# Maqam_v2.net
KiCad netlist of a schematic drawn in EAGLE
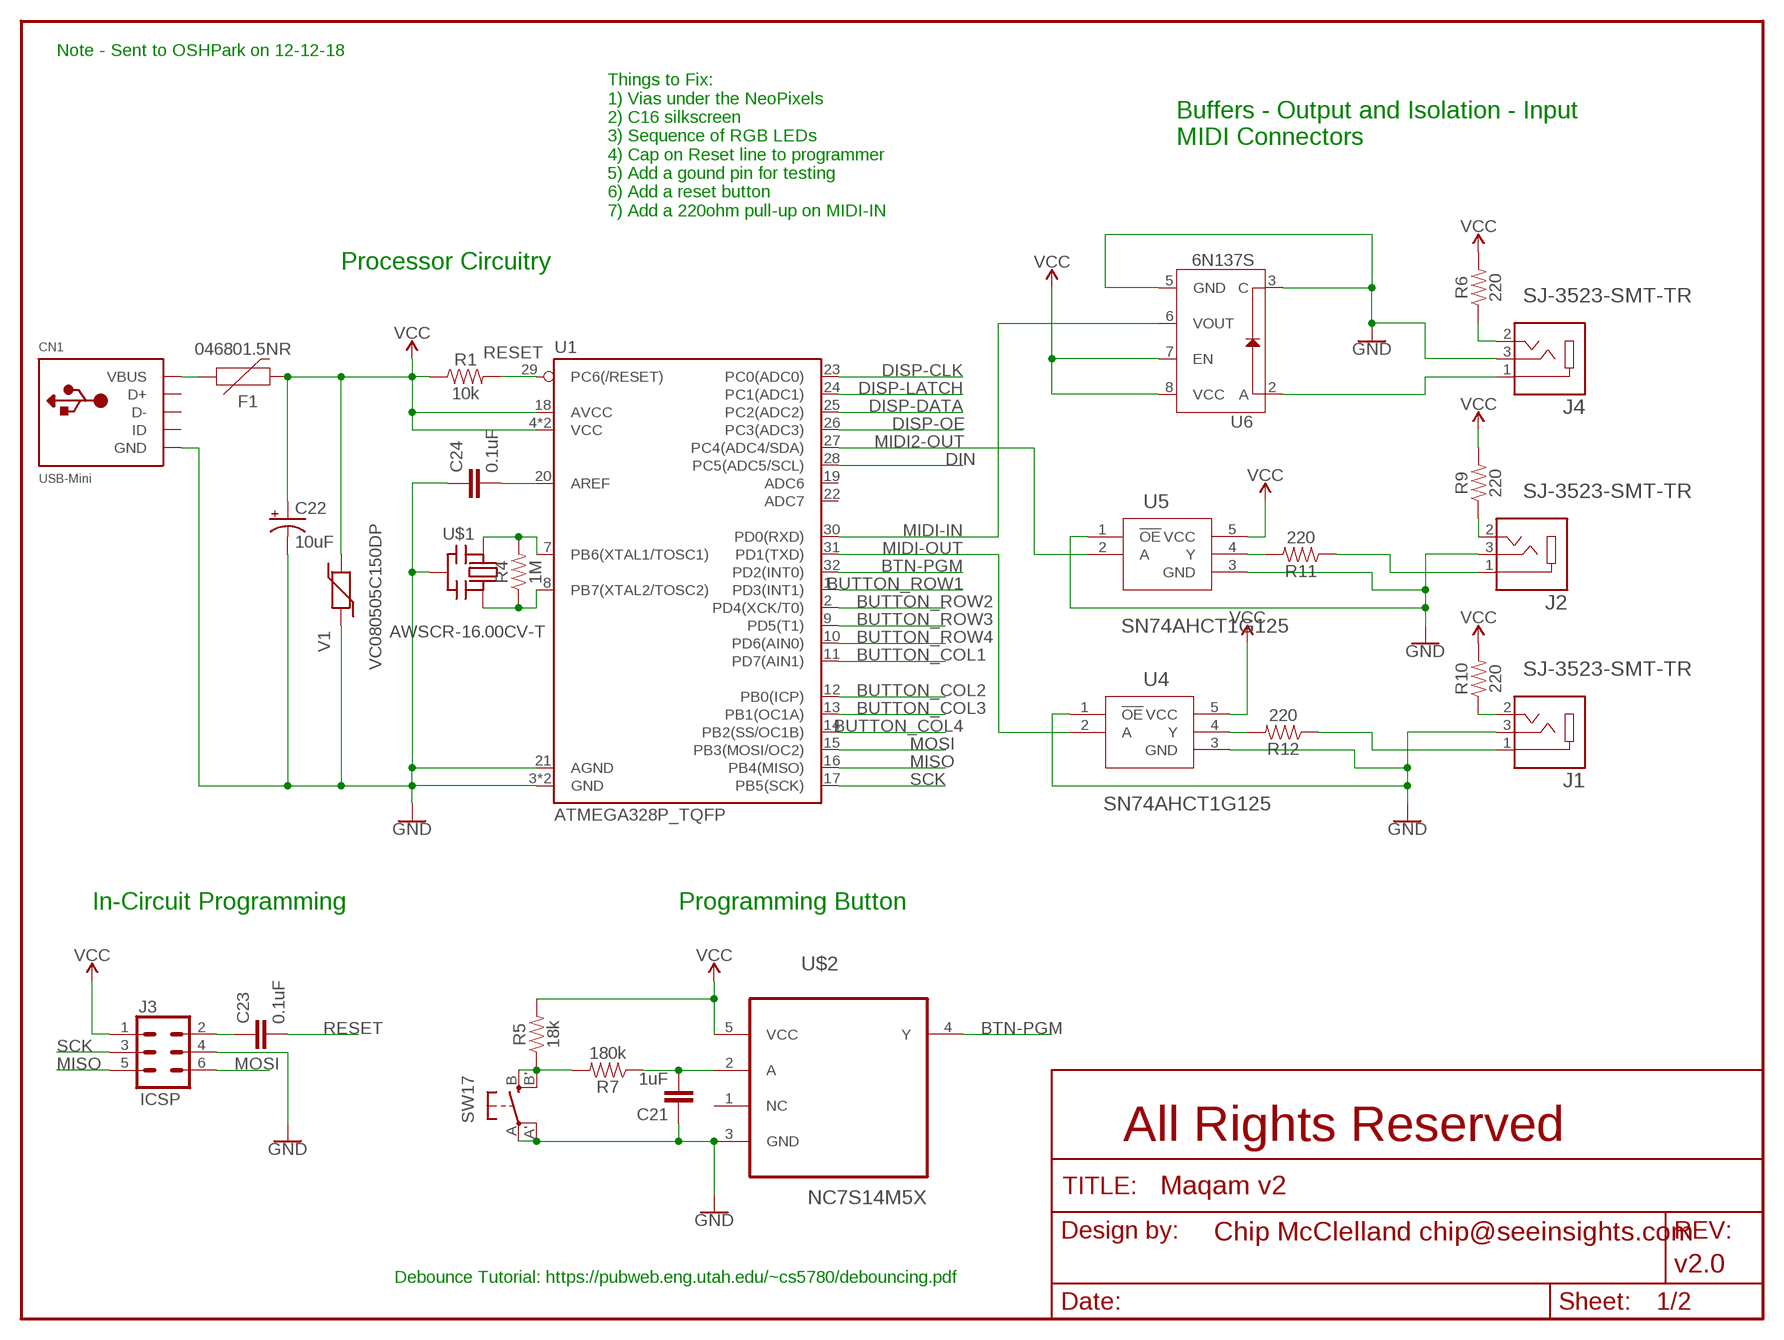
[diagram p0: schematic, sheet 1]
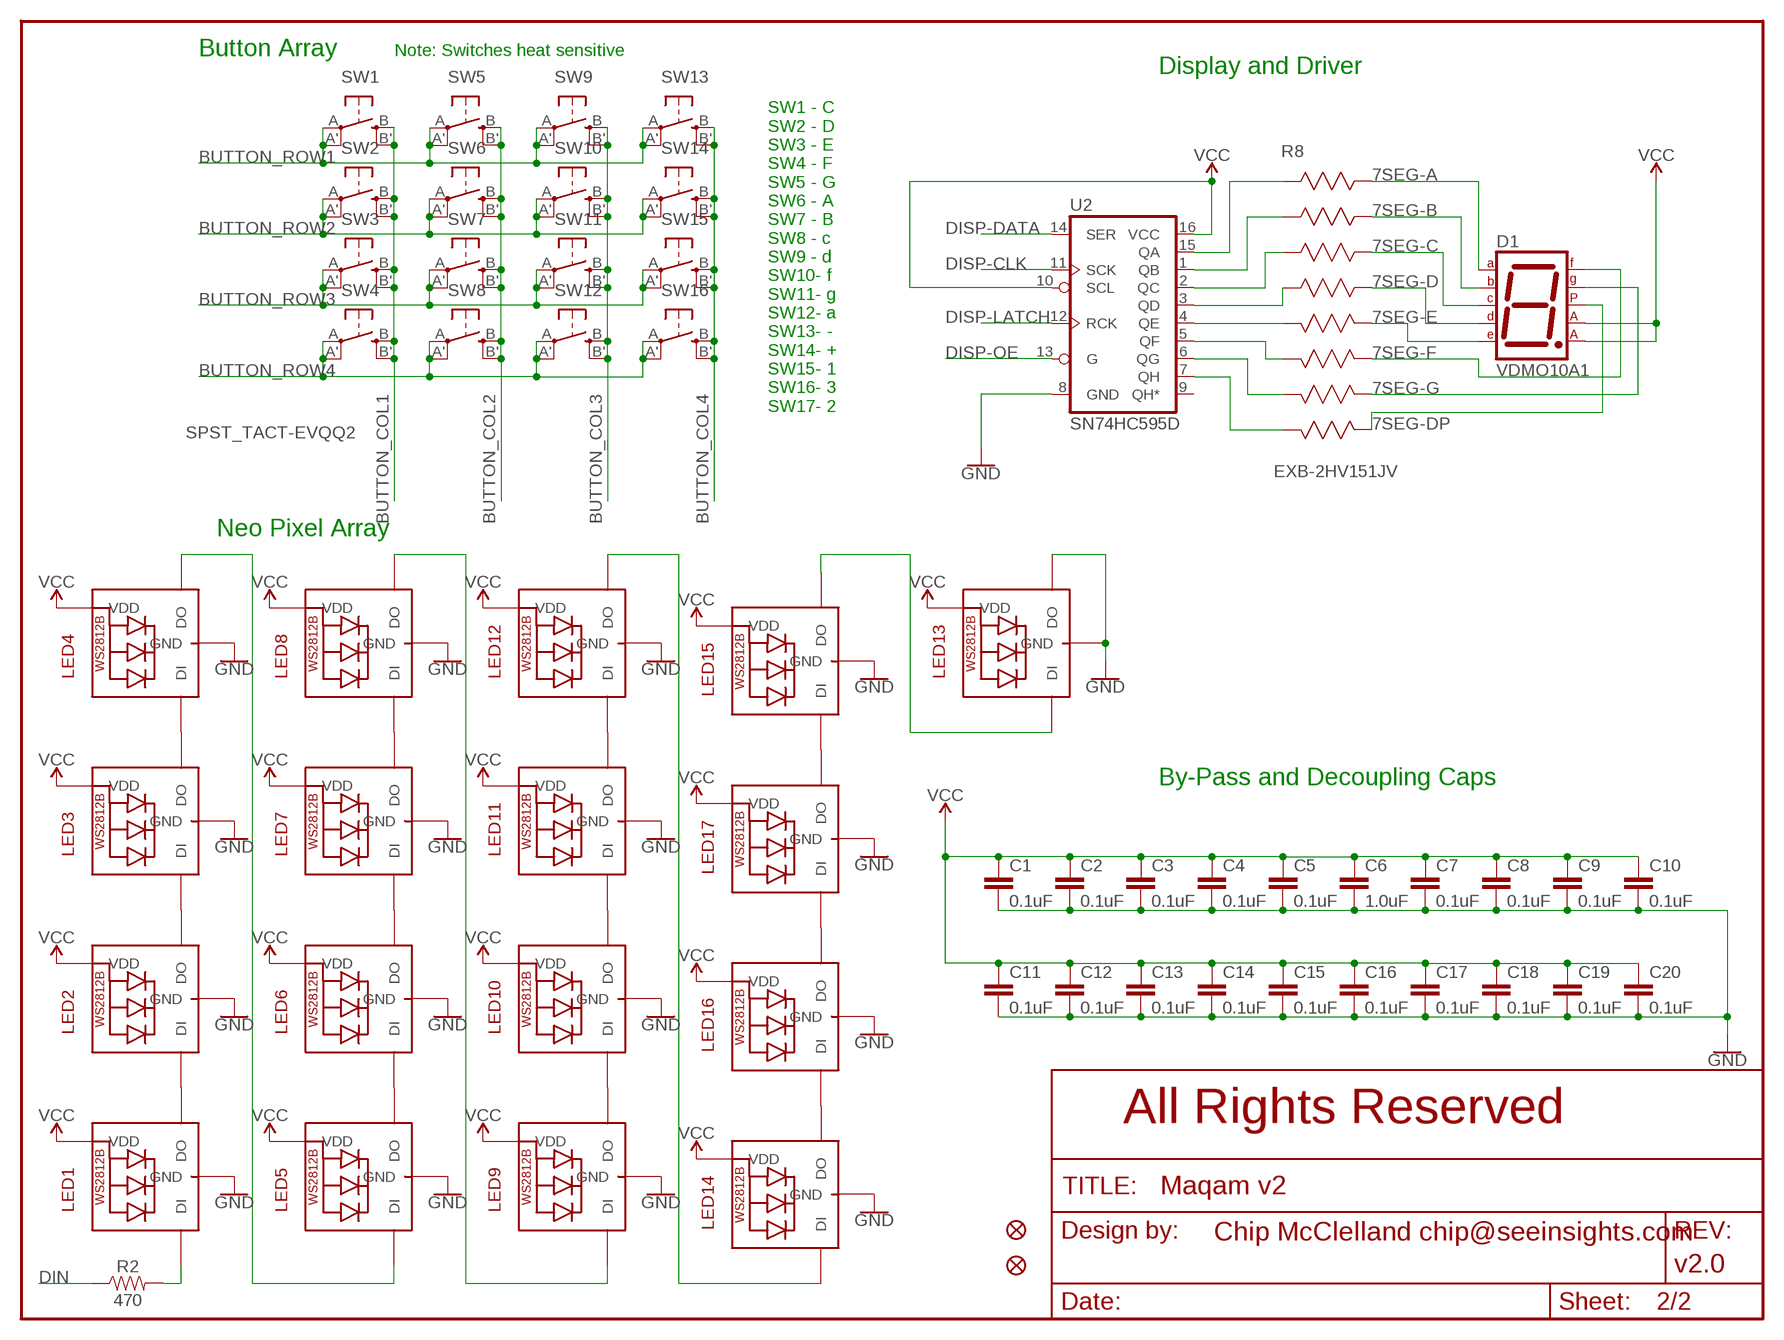
[diagram p1: schematic, sheet 2]

(export (version "E")
  (design (tool "Eeschema 10.0.6"))
  (components
    (comp (ref "C21")
      (value "1uF")
      (footprint "eagle-import:0805")
      (libsource (lib "eagle-import") (part "1.0UF-0805-25V-(+80/-20%)"))
    )
    (comp (ref "C22")
      (value "10uF")
      (footprint "eagle-import:EIA3216")
      (libsource (lib "eagle-import") (part "10UF-POLAR-EIA3216-16V-10%(TANT)"))
    )
    (comp (ref "C23")
      (value "0.1uF")
      (footprint "eagle-import:0805")
      (libsource (lib "eagle-import") (part "1.0UF-0805-25V-(+80/-20%)"))
    )
    (comp (ref "C24")
      (value "0.1uF")
      (footprint "eagle-import:0805")
      (libsource (lib "eagle-import") (part "1.0UF-0805-25V-(+80/-20%)"))
    )
    (comp (ref "CN1")
      (value "USB-Mini")
      (footprint "eagle-import:USB-MINIB")
      (libsource (lib "eagle-import") (part "USBMINIB"))
    )
    (comp (ref "F1")
      (value "046801.5NR")
      (footprint "eagle-import:1206")
      (libsource (lib "eagle-import") (part "PPTC_HALF-AMP"))
    )
    (comp (ref "FRAME2")
      (value "FRAME-LETTERNO_PACKAGE")
      (footprint "eagle-import:DUMMY")
      (fields
        (field (name "DESIGNER") "Chip McClelland chip@seeinsights.com")
        (field (name "REV") "v2.0")
        (field (name "VERSION") "v2.0")
        (field (name "DESIGNER_1") "Chip McClelland chip@seeinsights.com")
      )
      (libsource (lib "eagle-import") (part "FRAME-LETTERNO_PACKAGE"))
    )
    (comp (ref "J1")
      (value "SJ-3523-SMT-TR")
      (footprint "eagle-import:CUI_SJ-3523-SMT-TR")
      (fields (field (name "DIGI-KEY_PART_NUMBER") "CP-3523SJCT-ND") (field (name "MF") "CUI Inc."))
      (libsource (lib "eagle-import") (part "SJ-3523-SMT-TR"))
    )
    (comp (ref "J2")
      (value "SJ-3523-SMT-TR")
      (footprint "eagle-import:CUI_SJ-3523-SMT-TR")
      (fields (field (name "DIGI-KEY_PART_NUMBER") "CP-3523SJCT-ND") (field (name "MF") "CUI Inc."))
      (libsource (lib "eagle-import") (part "SJ-3523-SMT-TR"))
    )
    (comp (ref "J3")
      (value "ICSP")
      (footprint "eagle-import:2X3-SHROUDED")
      (libsource (lib "eagle-import") (part "CONN_03X2SHROUD"))
    )
    (comp (ref "J4")
      (value "SJ-3523-SMT-TR")
      (footprint "eagle-import:CUI_SJ-3523-SMT-TR")
      (fields (field (name "DIGI-KEY_PART_NUMBER") "CP-3523SJCT-ND") (field (name "MF") "CUI Inc."))
      (libsource (lib "eagle-import") (part "SJ-3523-SMT-TR"))
    )
    (comp (ref "R1")
      (value "10k")
      (footprint "eagle-import:0805")
      (libsource (lib "eagle-import") (part "RESISTOR0805"))
    )
    (comp (ref "R4")
      (value "1M")
      (footprint "eagle-import:0805")
      (libsource (lib "eagle-import") (part "RESISTOR0805"))
    )
    (comp (ref "R5")
      (value "18k")
      (footprint "eagle-import:0805")
      (libsource (lib "eagle-import") (part "RESISTOR0805"))
    )
    (comp (ref "R6")
      (value "220")
      (footprint "eagle-import:0805")
      (libsource (lib "eagle-import") (part "RESISTOR0805"))
    )
    (comp (ref "R7")
      (value "180k")
      (footprint "eagle-import:0805")
      (libsource (lib "eagle-import") (part "RESISTOR0805"))
    )
    (comp (ref "R9")
      (value "220")
      (footprint "eagle-import:0805")
      (libsource (lib "eagle-import") (part "RESISTOR0805"))
    )
    (comp (ref "R10")
      (value "220")
      (footprint "eagle-import:0805")
      (libsource (lib "eagle-import") (part "RESISTOR0805"))
    )
    (comp (ref "R11")
      (value "220")
      (footprint "eagle-import:0805")
      (libsource (lib "eagle-import") (part "RESISTOR0805"))
    )
    (comp (ref "R12")
      (value "220")
      (footprint "eagle-import:0805")
      (libsource (lib "eagle-import") (part "RESISTOR0805"))
    )
    (comp (ref "SW17")
      (value "SPST_TACT-EVQQ2")
      (footprint "eagle-import:EVQ-Q2")
      (libsource (lib "eagle-import") (part "SPST_TACT-EVQQ2"))
    )
    (comp (ref "U$1")
      (value "AWSCR-16.00CV-T")
      (footprint "eagle-import:AWSCR")
      (libsource (lib "eagle-import") (part "CERMOSCILL"))
    )
    (comp (ref "U$2")
      (value "NC7S14M5X")
      (footprint "eagle-import:SOT-23-5")
      (libsource (lib "eagle-import") (part "NC7S14M5X"))
    )
    (comp (ref "U1")
      (value "ATMEGA328P_TQFP")
      (footprint "eagle-import:TQFP32-08")
      (libsource (lib "eagle-import") (part "ATMEGA328P_TQFP"))
    )
    (comp (ref "U4")
      (value "SN74AHCT1G125")
      (footprint "eagle-import:DBV5-L")
      (fields (field (name "MANUFACTURER_PART_NUMBER") "SN74AHCT1G125DBVR"))
      (libsource (lib "eagle-import") (part "SN74AHCT1G125DBVRDBV5-L"))
    )
    (comp (ref "U5")
      (value "SN74AHCT1G125")
      (footprint "eagle-import:DBV5-L")
      (fields (field (name "MANUFACTURER_PART_NUMBER") "SN74AHCT1G125DBVR"))
      (libsource (lib "eagle-import") (part "SN74AHCT1G125DBVRDBV5-L"))
    )
    (comp (ref "U6")
      (value "6N137S")
      (footprint "eagle-import:8-SMD")
      (libsource (lib "eagle-import") (part "6N137S"))
    )
    (comp (ref "V1")
      (value "VC080505C150DP")
      (footprint "eagle-import:0805")
      (libsource (lib "eagle-import") (part "VARISTOR"))
    )
    (comp (ref "C1")
      (value "0.1uF")
      (footprint "eagle-import:0805")
      (libsource (lib "eagle-import") (part "1.0UF-0805-25V-(+80/-20%)"))
    )
    (comp (ref "C2")
      (value "0.1uF")
      (footprint "eagle-import:0805")
      (libsource (lib "eagle-import") (part "1.0UF-0805-25V-(+80/-20%)"))
    )
    (comp (ref "C3")
      (value "0.1uF")
      (footprint "eagle-import:0805")
      (libsource (lib "eagle-import") (part "1.0UF-0805-25V-(+80/-20%)"))
    )
    (comp (ref "C4")
      (value "0.1uF")
      (footprint "eagle-import:0805")
      (libsource (lib "eagle-import") (part "1.0UF-0805-25V-(+80/-20%)"))
    )
    (comp (ref "C5")
      (value "0.1uF")
      (footprint "eagle-import:0805")
      (libsource (lib "eagle-import") (part "1.0UF-0805-25V-(+80/-20%)"))
    )
    (comp (ref "C6")
      (value "1.0uF")
      (footprint "eagle-import:0805")
      (libsource (lib "eagle-import") (part "1.0UF-0805-25V-(+80/-20%)"))
    )
    (comp (ref "C7")
      (value "0.1uF")
      (footprint "eagle-import:0805")
      (libsource (lib "eagle-import") (part "1.0UF-0805-25V-(+80/-20%)"))
    )
    (comp (ref "C8")
      (value "0.1uF")
      (footprint "eagle-import:0805")
      (libsource (lib "eagle-import") (part "1.0UF-0805-25V-(+80/-20%)"))
    )
    (comp (ref "C9")
      (value "0.1uF")
      (footprint "eagle-import:0805")
      (libsource (lib "eagle-import") (part "1.0UF-0805-25V-(+80/-20%)"))
    )
    (comp (ref "C10")
      (value "0.1uF")
      (footprint "eagle-import:0805")
      (libsource (lib "eagle-import") (part "1.0UF-0805-25V-(+80/-20%)"))
    )
    (comp (ref "C11")
      (value "0.1uF")
      (footprint "eagle-import:0805")
      (libsource (lib "eagle-import") (part "1.0UF-0805-25V-(+80/-20%)"))
    )
    (comp (ref "C12")
      (value "0.1uF")
      (footprint "eagle-import:0805")
      (libsource (lib "eagle-import") (part "1.0UF-0805-25V-(+80/-20%)"))
    )
    (comp (ref "C13")
      (value "0.1uF")
      (footprint "eagle-import:0805")
      (libsource (lib "eagle-import") (part "1.0UF-0805-25V-(+80/-20%)"))
    )
    (comp (ref "C14")
      (value "0.1uF")
      (footprint "eagle-import:0805")
      (libsource (lib "eagle-import") (part "1.0UF-0805-25V-(+80/-20%)"))
    )
    (comp (ref "C15")
      (value "0.1uF")
      (footprint "eagle-import:0805")
      (libsource (lib "eagle-import") (part "1.0UF-0805-25V-(+80/-20%)"))
    )
    (comp (ref "C16")
      (value "0.1uF")
      (footprint "eagle-import:0805")
      (libsource (lib "eagle-import") (part "1.0UF-0805-25V-(+80/-20%)"))
    )
    (comp (ref "C17")
      (value "0.1uF")
      (footprint "eagle-import:0805")
      (libsource (lib "eagle-import") (part "1.0UF-0805-25V-(+80/-20%)"))
    )
    (comp (ref "C18")
      (value "0.1uF")
      (footprint "eagle-import:0805")
      (libsource (lib "eagle-import") (part "1.0UF-0805-25V-(+80/-20%)"))
    )
    (comp (ref "C19")
      (value "0.1uF")
      (footprint "eagle-import:0805")
      (libsource (lib "eagle-import") (part "1.0UF-0805-25V-(+80/-20%)"))
    )
    (comp (ref "C20")
      (value "0.1uF")
      (footprint "eagle-import:0805")
      (libsource (lib "eagle-import") (part "1.0UF-0805-25V-(+80/-20%)"))
    )
    (comp (ref "D1")
      (value "VDMO10A1")
      (footprint "eagle-import:7-SEG-SMD")
      (libsource (lib "eagle-import") (part "VDMO10A1"))
    )
    (comp (ref "FD1")
      (value "FIDUCIALUFIDUCIAL")
      (footprint "eagle-import:FIDUCIAL-MICRO")
      (libsource (lib "eagle-import") (part "FIDUCIALUFIDUCIAL"))
    )
    (comp (ref "FD2")
      (value "FIDUCIALUFIDUCIAL")
      (footprint "eagle-import:FIDUCIAL-MICRO")
      (libsource (lib "eagle-import") (part "FIDUCIALUFIDUCIAL"))
    )
    (comp (ref "FRAME1")
      (value "FRAME-LETTERNO_PACKAGE")
      (footprint "eagle-import:DUMMY")
      (fields
        (field (name "DESIGNER") "Chip McClelland chip@seeinsights.com")
        (field (name "REV") "v2.0")
        (field (name "VERSION") "v2.0")
        (field (name "DESIGNER_1") "Chip McClelland chip@seeinsights.com")
      )
      (libsource (lib "eagle-import") (part "FRAME-LETTERNO_PACKAGE"))
    )
    (comp (ref "LED1")
      (value "WS2812B3535")
      (footprint "eagle-import:LED3535")
      (libsource (lib "eagle-import") (part "WS2812B3535"))
    )
    (comp (ref "LED2")
      (value "WS2812B3535")
      (footprint "eagle-import:LED3535")
      (libsource (lib "eagle-import") (part "WS2812B3535"))
    )
    (comp (ref "LED3")
      (value "WS2812B3535")
      (footprint "eagle-import:LED3535")
      (libsource (lib "eagle-import") (part "WS2812B3535"))
    )
    (comp (ref "LED4")
      (value "WS2812B3535")
      (footprint "eagle-import:LED3535")
      (libsource (lib "eagle-import") (part "WS2812B3535"))
    )
    (comp (ref "LED5")
      (value "WS2812B3535")
      (footprint "eagle-import:LED3535")
      (libsource (lib "eagle-import") (part "WS2812B3535"))
    )
    (comp (ref "LED6")
      (value "WS2812B3535")
      (footprint "eagle-import:LED3535")
      (libsource (lib "eagle-import") (part "WS2812B3535"))
    )
    (comp (ref "LED7")
      (value "WS2812B3535")
      (footprint "eagle-import:LED3535")
      (libsource (lib "eagle-import") (part "WS2812B3535"))
    )
    (comp (ref "LED8")
      (value "WS2812B3535")
      (footprint "eagle-import:LED3535")
      (libsource (lib "eagle-import") (part "WS2812B3535"))
    )
    (comp (ref "LED9")
      (value "WS2812B3535")
      (footprint "eagle-import:LED3535")
      (libsource (lib "eagle-import") (part "WS2812B3535"))
    )
    (comp (ref "LED10")
      (value "WS2812B3535")
      (footprint "eagle-import:LED3535")
      (libsource (lib "eagle-import") (part "WS2812B3535"))
    )
    (comp (ref "LED11")
      (value "WS2812B3535")
      (footprint "eagle-import:LED3535")
      (libsource (lib "eagle-import") (part "WS2812B3535"))
    )
    (comp (ref "LED12")
      (value "WS2812B3535")
      (footprint "eagle-import:LED3535")
      (libsource (lib "eagle-import") (part "WS2812B3535"))
    )
    (comp (ref "LED13")
      (value "WS2812B3535")
      (footprint "eagle-import:LED3535")
      (libsource (lib "eagle-import") (part "WS2812B3535"))
    )
    (comp (ref "LED14")
      (value "WS2812B3535")
      (footprint "eagle-import:LED3535")
      (libsource (lib "eagle-import") (part "WS2812B3535"))
    )
    (comp (ref "LED15")
      (value "WS2812B3535")
      (footprint "eagle-import:LED3535")
      (libsource (lib "eagle-import") (part "WS2812B3535"))
    )
    (comp (ref "LED16")
      (value "WS2812B3535")
      (footprint "eagle-import:LED3535")
      (libsource (lib "eagle-import") (part "WS2812B3535"))
    )
    (comp (ref "LED17")
      (value "WS2812B3535")
      (footprint "eagle-import:LED3535")
      (libsource (lib "eagle-import") (part "WS2812B3535"))
    )
    (comp (ref "R2")
      (value "470")
      (footprint "eagle-import:0805")
      (libsource (lib "eagle-import") (part "RESISTOR0805"))
    )
    (comp (ref "R8")
      (value "EXB-2HV151JV")
      (footprint "eagle-import:EXB2HV-L")
      (fields (field (name "MANUFACTURER_PART_NUMBER") "EXB2HV103JV"))
      (libsource (lib "eagle-import") (part "EXB-2HV103JVEXB2HV-L"))
    )
    (comp (ref "SW1")
      (value "SPST_TACT-EVQQ2")
      (footprint "eagle-import:EVQ-Q2")
      (libsource (lib "eagle-import") (part "SPST_TACT-EVQQ2"))
    )
    (comp (ref "SW2")
      (value "SPST_TACT-EVQQ2")
      (footprint "eagle-import:EVQ-Q2")
      (libsource (lib "eagle-import") (part "SPST_TACT-EVQQ2"))
    )
    (comp (ref "SW3")
      (value "SPST_TACT-EVQQ2")
      (footprint "eagle-import:EVQ-Q2")
      (libsource (lib "eagle-import") (part "SPST_TACT-EVQQ2"))
    )
    (comp (ref "SW4")
      (value "SPST_TACT-EVQQ2")
      (footprint "eagle-import:EVQ-Q2")
      (libsource (lib "eagle-import") (part "SPST_TACT-EVQQ2"))
    )
    (comp (ref "SW5")
      (value "SPST_TACT-EVQQ2")
      (footprint "eagle-import:EVQ-Q2")
      (libsource (lib "eagle-import") (part "SPST_TACT-EVQQ2"))
    )
    (comp (ref "SW6")
      (value "SPST_TACT-EVQQ2")
      (footprint "eagle-import:EVQ-Q2")
      (libsource (lib "eagle-import") (part "SPST_TACT-EVQQ2"))
    )
    (comp (ref "SW7")
      (value "SPST_TACT-EVQQ2")
      (footprint "eagle-import:EVQ-Q2")
      (libsource (lib "eagle-import") (part "SPST_TACT-EVQQ2"))
    )
    (comp (ref "SW8")
      (value "SPST_TACT-EVQQ2")
      (footprint "eagle-import:EVQ-Q2")
      (libsource (lib "eagle-import") (part "SPST_TACT-EVQQ2"))
    )
    (comp (ref "SW9")
      (value "SPST_TACT-EVQQ2")
      (footprint "eagle-import:EVQ-Q2")
      (libsource (lib "eagle-import") (part "SPST_TACT-EVQQ2"))
    )
    (comp (ref "SW10")
      (value "SPST_TACT-EVQQ2")
      (footprint "eagle-import:EVQ-Q2")
      (libsource (lib "eagle-import") (part "SPST_TACT-EVQQ2"))
    )
    (comp (ref "SW11")
      (value "SPST_TACT-EVQQ2")
      (footprint "eagle-import:EVQ-Q2")
      (libsource (lib "eagle-import") (part "SPST_TACT-EVQQ2"))
    )
    (comp (ref "SW12")
      (value "SPST_TACT-EVQQ2")
      (footprint "eagle-import:EVQ-Q2")
      (libsource (lib "eagle-import") (part "SPST_TACT-EVQQ2"))
    )
    (comp (ref "SW13")
      (value "SPST_TACT-EVQQ2")
      (footprint "eagle-import:EVQ-Q2")
      (libsource (lib "eagle-import") (part "SPST_TACT-EVQQ2"))
    )
    (comp (ref "SW14")
      (value "SPST_TACT-EVQQ2")
      (footprint "eagle-import:EVQ-Q2")
      (libsource (lib "eagle-import") (part "SPST_TACT-EVQQ2"))
    )
    (comp (ref "SW15")
      (value "SPST_TACT-EVQQ2")
      (footprint "eagle-import:EVQ-Q2")
      (libsource (lib "eagle-import") (part "SPST_TACT-EVQQ2"))
    )
    (comp (ref "SW16")
      (value "SPST_TACT-EVQQ2")
      (footprint "eagle-import:EVQ-Q2")
      (libsource (lib "eagle-import") (part "SPST_TACT-EVQQ2"))
    )
    (comp (ref "U2")
      (value "SN74HC595D")
      (footprint "eagle-import:SO16")
      (libsource (lib "eagle-import") (part "74595DHC"))
    )
  )
  (nets
    (net (code "1") (name "7SEG-A") (class "Default")
      (node (ref "D1") (pin "7SEG7") (pinfunction "A_7SEG7") (pintype "passive"))
      (node (ref "R8") (pin "16") (pinfunction "162_16") (pintype "passive"))
    )
    (net (code "2") (name "7SEG-B") (class "Default")
      (node (ref "D1") (pin "7SEG6") (pinfunction "B_7SEG6") (pintype "passive"))
      (node (ref "R8") (pin "15") (pinfunction "154_15") (pintype "passive"))
    )
    (net (code "3") (name "7SEG-C") (class "Default")
      (node (ref "D1") (pin "7SEG4") (pinfunction "C_7SEG4") (pintype "passive"))
      (node (ref "R8") (pin "14") (pinfunction "146_14") (pintype "passive"))
    )
    (net (code "4") (name "7SEG-D") (class "Default")
      (node (ref "D1") (pin "7SEG2") (pinfunction "D_7SEG2") (pintype "passive"))
      (node (ref "R8") (pin "13") (pinfunction "138_13") (pintype "passive"))
    )
    (net (code "5") (name "7SEG-DP") (class "Default")
      (node (ref "D1") (pin "7SEG5") (pinfunction "DP_7SEG5") (pintype "passive"))
      (node (ref "R8") (pin "9") (pinfunction "912_9") (pintype "passive"))
    )
    (net (code "6") (name "7SEG-E") (class "Default")
      (node (ref "D1") (pin "7SEG1") (pinfunction "E_7SEG1") (pintype "passive"))
      (node (ref "R8") (pin "12") (pinfunction "1211_12") (pintype "passive"))
    )
    (net (code "7") (name "7SEG-F") (class "Default")
      (node (ref "D1") (pin "7SEG9") (pinfunction "F_7SEG9") (pintype "passive"))
      (node (ref "R8") (pin "11") (pinfunction "1110_11") (pintype "passive"))
    )
    (net (code "8") (name "7SEG-G") (class "Default")
      (node (ref "D1") (pin "7SEG10") (pinfunction "G_7SEG10") (pintype "passive"))
      (node (ref "R8") (pin "10") (pinfunction "109_10") (pintype "passive"))
    )
    (net (code "9") (name "BTN-PGM") (class "Default")
      (node (ref "U$2") (pin "4") (pinfunction "Y_4") (pintype "output"))
      (node (ref "U1") (pin "32") (pinfunction "PD2(INT0)_32") (pintype "bidirectional"))
    )
    (net (code "10") (name "BUTTON_COL1") (class "Default")
      (node (ref "SW1") (pin "B") (pinfunction "S_B") (pintype "passive"))
      (node (ref "SW1") (pin "B'") (pinfunction "S1_B'") (pintype "passive"))
      (node (ref "SW2") (pin "B") (pinfunction "S_B") (pintype "passive"))
      (node (ref "SW2") (pin "B'") (pinfunction "S1_B'") (pintype "passive"))
      (node (ref "SW3") (pin "B") (pinfunction "S_B") (pintype "passive"))
      (node (ref "SW3") (pin "B'") (pinfunction "S1_B'") (pintype "passive"))
      (node (ref "SW4") (pin "B") (pinfunction "S_B") (pintype "passive"))
      (node (ref "SW4") (pin "B'") (pinfunction "S1_B'") (pintype "passive"))
      (node (ref "U1") (pin "11") (pinfunction "PD7(AIN1)_11") (pintype "bidirectional"))
    )
    (net (code "11") (name "BUTTON_COL2") (class "Default")
      (node (ref "SW5") (pin "B") (pinfunction "S_B") (pintype "passive"))
      (node (ref "SW5") (pin "B'") (pinfunction "S1_B'") (pintype "passive"))
      (node (ref "SW6") (pin "B") (pinfunction "S_B") (pintype "passive"))
      (node (ref "SW6") (pin "B'") (pinfunction "S1_B'") (pintype "passive"))
      (node (ref "SW7") (pin "B") (pinfunction "S_B") (pintype "passive"))
      (node (ref "SW7") (pin "B'") (pinfunction "S1_B'") (pintype "passive"))
      (node (ref "SW8") (pin "B") (pinfunction "S_B") (pintype "passive"))
      (node (ref "SW8") (pin "B'") (pinfunction "S1_B'") (pintype "passive"))
      (node (ref "U1") (pin "12") (pinfunction "PB0(ICP)_12") (pintype "bidirectional"))
    )
    (net (code "12") (name "BUTTON_COL3") (class "Default")
      (node (ref "SW10") (pin "B") (pinfunction "S_B") (pintype "passive"))
      (node (ref "SW10") (pin "B'") (pinfunction "S1_B'") (pintype "passive"))
      (node (ref "SW11") (pin "B") (pinfunction "S_B") (pintype "passive"))
      (node (ref "SW11") (pin "B'") (pinfunction "S1_B'") (pintype "passive"))
      (node (ref "SW12") (pin "B") (pinfunction "S_B") (pintype "passive"))
      (node (ref "SW12") (pin "B'") (pinfunction "S1_B'") (pintype "passive"))
      (node (ref "SW9") (pin "B") (pinfunction "S_B") (pintype "passive"))
      (node (ref "SW9") (pin "B'") (pinfunction "S1_B'") (pintype "passive"))
      (node (ref "U1") (pin "13") (pinfunction "PB1(OC1A)_13") (pintype "bidirectional"))
    )
    (net (code "13") (name "BUTTON_COL4") (class "Default")
      (node (ref "SW13") (pin "B") (pinfunction "S_B") (pintype "passive"))
      (node (ref "SW13") (pin "B'") (pinfunction "S1_B'") (pintype "passive"))
      (node (ref "SW14") (pin "B") (pinfunction "S_B") (pintype "passive"))
      (node (ref "SW14") (pin "B'") (pinfunction "S1_B'") (pintype "passive"))
      (node (ref "SW15") (pin "B") (pinfunction "S_B") (pintype "passive"))
      (node (ref "SW15") (pin "B'") (pinfunction "S1_B'") (pintype "passive"))
      (node (ref "SW16") (pin "B") (pinfunction "S_B") (pintype "passive"))
      (node (ref "SW16") (pin "B'") (pinfunction "S1_B'") (pintype "passive"))
      (node (ref "U1") (pin "14") (pinfunction "PB2(SS/OC1B)_14") (pintype "bidirectional"))
    )
    (net (code "14") (name "BUTTON_ROW1") (class "Default")
      (node (ref "SW1") (pin "A") (pinfunction "P_A") (pintype "passive"))
      (node (ref "SW1") (pin "A'") (pinfunction "P1_A'") (pintype "passive"))
      (node (ref "SW13") (pin "A") (pinfunction "P_A") (pintype "passive"))
      (node (ref "SW13") (pin "A'") (pinfunction "P1_A'") (pintype "passive"))
      (node (ref "SW5") (pin "A") (pinfunction "P_A") (pintype "passive"))
      (node (ref "SW5") (pin "A'") (pinfunction "P1_A'") (pintype "passive"))
      (node (ref "SW9") (pin "A") (pinfunction "P_A") (pintype "passive"))
      (node (ref "SW9") (pin "A'") (pinfunction "P1_A'") (pintype "passive"))
      (node (ref "U1") (pin "1") (pinfunction "PD3(INT1)_1") (pintype "bidirectional"))
    )
    (net (code "15") (name "BUTTON_ROW2") (class "Default")
      (node (ref "SW10") (pin "A") (pinfunction "P_A") (pintype "passive"))
      (node (ref "SW10") (pin "A'") (pinfunction "P1_A'") (pintype "passive"))
      (node (ref "SW14") (pin "A") (pinfunction "P_A") (pintype "passive"))
      (node (ref "SW14") (pin "A'") (pinfunction "P1_A'") (pintype "passive"))
      (node (ref "SW2") (pin "A") (pinfunction "P_A") (pintype "passive"))
      (node (ref "SW2") (pin "A'") (pinfunction "P1_A'") (pintype "passive"))
      (node (ref "SW6") (pin "A") (pinfunction "P_A") (pintype "passive"))
      (node (ref "SW6") (pin "A'") (pinfunction "P1_A'") (pintype "passive"))
      (node (ref "U1") (pin "2") (pinfunction "PD4(XCK/T0)_2") (pintype "bidirectional"))
    )
    (net (code "16") (name "BUTTON_ROW3") (class "Default")
      (node (ref "SW11") (pin "A") (pinfunction "P_A") (pintype "passive"))
      (node (ref "SW11") (pin "A'") (pinfunction "P1_A'") (pintype "passive"))
      (node (ref "SW15") (pin "A") (pinfunction "P_A") (pintype "passive"))
      (node (ref "SW15") (pin "A'") (pinfunction "P1_A'") (pintype "passive"))
      (node (ref "SW3") (pin "A") (pinfunction "P_A") (pintype "passive"))
      (node (ref "SW3") (pin "A'") (pinfunction "P1_A'") (pintype "passive"))
      (node (ref "SW7") (pin "A") (pinfunction "P_A") (pintype "passive"))
      (node (ref "SW7") (pin "A'") (pinfunction "P1_A'") (pintype "passive"))
      (node (ref "U1") (pin "9") (pinfunction "PD5(T1)_9") (pintype "bidirectional"))
    )
    (net (code "17") (name "BUTTON_ROW4") (class "Default")
      (node (ref "SW12") (pin "A") (pinfunction "P_A") (pintype "passive"))
      (node (ref "SW12") (pin "A'") (pinfunction "P1_A'") (pintype "passive"))
      (node (ref "SW16") (pin "A") (pinfunction "P_A") (pintype "passive"))
      (node (ref "SW16") (pin "A'") (pinfunction "P1_A'") (pintype "passive"))
      (node (ref "SW4") (pin "A") (pinfunction "P_A") (pintype "passive"))
      (node (ref "SW4") (pin "A'") (pinfunction "P1_A'") (pintype "passive"))
      (node (ref "SW8") (pin "A") (pinfunction "P_A") (pintype "passive"))
      (node (ref "SW8") (pin "A'") (pinfunction "P1_A'") (pintype "passive"))
      (node (ref "U1") (pin "10") (pinfunction "PD6(AIN0)_10") (pintype "bidirectional"))
    )
    (net (code "18") (name "DIN") (class "Default")
      (node (ref "R2") (pin "1") (pinfunction "1_1") (pintype "passive"))
      (node (ref "U1") (pin "28") (pinfunction "PC5(ADC5/SCL)_28") (pintype "bidirectional"))
    )
    (net (code "19") (name "DISP-CLK") (class "Default")
      (node (ref "U1") (pin "23") (pinfunction "PC0(ADC0)_23") (pintype "bidirectional"))
      (node (ref "U2") (pin "11") (pinfunction "SCK_11") (pintype "input"))
    )
    (net (code "20") (name "DISP-DATA") (class "Default")
      (node (ref "U1") (pin "25") (pinfunction "PC2(ADC2)_25") (pintype "bidirectional"))
      (node (ref "U2") (pin "14") (pinfunction "SER_14") (pintype "input"))
    )
    (net (code "21") (name "DISP-LATCH") (class "Default")
      (node (ref "U1") (pin "24") (pinfunction "PC1(ADC1)_24") (pintype "bidirectional"))
      (node (ref "U2") (pin "12") (pinfunction "RCK_12") (pintype "input"))
    )
    (net (code "22") (name "DISP-OE") (class "Default")
      (node (ref "U1") (pin "26") (pinfunction "PC3(ADC3)_26") (pintype "bidirectional"))
      (node (ref "U2") (pin "13") (pinfunction "G_13") (pintype "input"))
    )
    (net (code "23") (name "GND") (class "Default")
      (node (ref "C1") (pin "2") (pinfunction "2_2") (pintype "passive"))
      (node (ref "C10") (pin "2") (pinfunction "2_2") (pintype "passive"))
      (node (ref "C11") (pin "2") (pinfunction "2_2") (pintype "passive"))
      (node (ref "C12") (pin "2") (pinfunction "2_2") (pintype "passive"))
      (node (ref "C13") (pin "2") (pinfunction "2_2") (pintype "passive"))
      (node (ref "C14") (pin "2") (pinfunction "2_2") (pintype "passive"))
      (node (ref "C15") (pin "2") (pinfunction "2_2") (pintype "passive"))
      (node (ref "C16") (pin "2") (pinfunction "2_2") (pintype "passive"))
      (node (ref "C17") (pin "2") (pinfunction "2_2") (pintype "passive"))
      (node (ref "C18") (pin "2") (pinfunction "2_2") (pintype "passive"))
      (node (ref "C19") (pin "2") (pinfunction "2_2") (pintype "passive"))
      (node (ref "C2") (pin "2") (pinfunction "2_2") (pintype "passive"))
      (node (ref "C20") (pin "2") (pinfunction "2_2") (pintype "passive"))
      (node (ref "C21") (pin "1") (pinfunction "1_1") (pintype "passive"))
      (node (ref "C22") (pin "-") (pinfunction "-_-") (pintype "passive"))
      (node (ref "C24") (pin "1") (pinfunction "1_1") (pintype "passive"))
      (node (ref "C3") (pin "2") (pinfunction "2_2") (pintype "passive"))
      (node (ref "C4") (pin "2") (pinfunction "2_2") (pintype "passive"))
      (node (ref "C5") (pin "2") (pinfunction "2_2") (pintype "passive"))
      (node (ref "C6") (pin "2") (pinfunction "2_2") (pintype "passive"))
      (node (ref "C7") (pin "2") (pinfunction "2_2") (pintype "passive"))
      (node (ref "C8") (pin "2") (pinfunction "2_2") (pintype "passive"))
      (node (ref "C9") (pin "2") (pinfunction "2_2") (pintype "passive"))
      (node (ref "CN1") (pin "GND") (pinfunction "GND_GND") (pintype "power_in"))
      (node (ref "J1") (pin "3") (pinfunction "3_3") (pintype "passive"))
      (node (ref "J2") (pin "3") (pinfunction "3_3") (pintype "passive"))
      (node (ref "J3") (pin "4") (pinfunction "4_4") (pintype "bidirectional"))
      (node (ref "J4") (pin "3") (pinfunction "3_3") (pintype "passive"))
      (node (ref "LED1") (pin "4") (pinfunction "GND_4") (pintype "power_in"))
      (node (ref "LED10") (pin "4") (pinfunction "GND_4") (pintype "power_in"))
      (node (ref "LED11") (pin "4") (pinfunction "GND_4") (pintype "power_in"))
      (node (ref "LED12") (pin "4") (pinfunction "GND_4") (pintype "power_in"))
      (node (ref "LED13") (pin "3") (pinfunction "DO_3") (pintype "output"))
      (node (ref "LED13") (pin "4") (pinfunction "GND_4") (pintype "power_in"))
      (node (ref "LED14") (pin "4") (pinfunction "GND_4") (pintype "power_in"))
      (node (ref "LED15") (pin "4") (pinfunction "GND_4") (pintype "power_in"))
      (node (ref "LED16") (pin "4") (pinfunction "GND_4") (pintype "power_in"))
      (node (ref "LED17") (pin "4") (pinfunction "GND_4") (pintype "power_in"))
      (node (ref "LED2") (pin "4") (pinfunction "GND_4") (pintype "power_in"))
      (node (ref "LED3") (pin "4") (pinfunction "GND_4") (pintype "power_in"))
      (node (ref "LED4") (pin "4") (pinfunction "GND_4") (pintype "power_in"))
      (node (ref "LED5") (pin "4") (pinfunction "GND_4") (pintype "power_in"))
      (node (ref "LED6") (pin "4") (pinfunction "GND_4") (pintype "power_in"))
      (node (ref "LED7") (pin "4") (pinfunction "GND_4") (pintype "power_in"))
      (node (ref "LED8") (pin "4") (pinfunction "GND_4") (pintype "power_in"))
      (node (ref "LED9") (pin "4") (pinfunction "GND_4") (pintype "power_in"))
      (node (ref "SW17") (pin "A") (pinfunction "P_A") (pintype "passive"))
      (node (ref "SW17") (pin "A'") (pinfunction "P1_A'") (pintype "passive"))
      (node (ref "U$1") (pin "2") (pinfunction "GND_2") (pintype "bidirectional"))
      (node (ref "U$2") (pin "3") (pinfunction "GND_3") (pintype "passive"))
      (node (ref "U1") (pin "21") (pinfunction "AGND_21") (pintype "bidirectional"))
      (node (ref "U1") (pin "3") (pinfunction "GND_3") (pintype "bidirectional"))
      (node (ref "U1") (pin "5") (pinfunction "GND_5") (pintype "bidirectional"))
      (node (ref "U2") (pin "8") (pinfunction "GND_8") (pintype "power_in"))
      (node (ref "U4") (pin "1") (pinfunction "~{OE}_1") (pintype "input"))
      (node (ref "U4") (pin "3") (pinfunction "GND_3") (pintype "power_in"))
      (node (ref "U5") (pin "1") (pinfunction "~{OE}_1") (pintype "input"))
      (node (ref "U5") (pin "3") (pinfunction "GND_3") (pintype "power_in"))
      (node (ref "U6") (pin "3") (pinfunction "C_3") (pintype "bidirectional"))
      (node (ref "U6") (pin "5") (pinfunction "GND_5") (pintype "bidirectional"))
      (node (ref "V1") (pin "1") (pinfunction "1_1") (pintype "passive"))
    )
    (net (code "24") (name "MIDI-IN") (class "Default")
      (node (ref "U1") (pin "30") (pinfunction "PD0(RXD)_30") (pintype "bidirectional"))
      (node (ref "U6") (pin "6") (pinfunction "VOUT_6") (pintype "bidirectional"))
    )
    (net (code "25") (name "MIDI-OUT") (class "Default")
      (node (ref "U1") (pin "31") (pinfunction "PD1(TXD)_31") (pintype "bidirectional"))
      (node (ref "U4") (pin "2") (pinfunction "A_2") (pintype "input"))
    )
    (net (code "26") (name "MIDI2-OUT") (class "Default")
      (node (ref "U1") (pin "27") (pinfunction "PC4(ADC4/SDA)_27") (pintype "bidirectional"))
      (node (ref "U5") (pin "2") (pinfunction "A_2") (pintype "input"))
    )
    (net (code "27") (name "MISO") (class "Default")
      (node (ref "J3") (pin "5") (pinfunction "5_5") (pintype "bidirectional"))
      (node (ref "U1") (pin "16") (pinfunction "PB4(MISO)_16") (pintype "bidirectional"))
    )
    (net (code "28") (name "MOSI") (class "Default")
      (node (ref "J3") (pin "6") (pinfunction "6_6") (pintype "bidirectional"))
      (node (ref "U1") (pin "15") (pinfunction "PB3(MOSI/OC2)_15") (pintype "bidirectional"))
    )
    (net (code "29") (name "Net-(C23-Pad1)") (class "Default")
      (node (ref "C23") (pin "1") (pinfunction "1_1") (pintype "passive"))
      (node (ref "J3") (pin "2") (pinfunction "2_2") (pintype "bidirectional"))
    )
    (net (code "30") (name "Net-(CN1-PadVBUS)") (class "Default")
      (node (ref "CN1") (pin "VBUS") (pinfunction "VBUS_VBUS") (pintype "power_in"))
      (node (ref "F1") (pin "1") (pinfunction "1_1") (pintype "bidirectional"))
    )
    (net (code "31") (name "Net-(J1-Pad1)") (class "Default")
      (node (ref "J1") (pin "1") (pinfunction "1_1") (pintype "passive"))
      (node (ref "R12") (pin "1") (pinfunction "1_1") (pintype "passive"))
    )
    (net (code "32") (name "Net-(J1-Pad2)") (class "Default")
      (node (ref "J1") (pin "2") (pinfunction "2_2") (pintype "passive"))
      (node (ref "R10") (pin "1") (pinfunction "1_1") (pintype "passive"))
    )
    (net (code "33") (name "Net-(J2-Pad1)") (class "Default")
      (node (ref "J2") (pin "1") (pinfunction "1_1") (pintype "passive"))
      (node (ref "R11") (pin "1") (pinfunction "1_1") (pintype "passive"))
    )
    (net (code "34") (name "Net-(J2-Pad2)") (class "Default")
      (node (ref "J2") (pin "2") (pinfunction "2_2") (pintype "passive"))
      (node (ref "R9") (pin "1") (pinfunction "1_1") (pintype "passive"))
    )
    (net (code "35") (name "Net-(J4-Pad2)") (class "Default")
      (node (ref "J4") (pin "2") (pinfunction "2_2") (pintype "passive"))
      (node (ref "R6") (pin "1") (pinfunction "1_1") (pintype "passive"))
    )
    (net (code "36") (name "Net-(LED1-DI)") (class "Default")
      (node (ref "LED1") (pin "1") (pinfunction "DI_1") (pintype "input"))
      (node (ref "R2") (pin "2") (pinfunction "2_2") (pintype "passive"))
    )
    (net (code "37") (name "Net-(LED1-DO)") (class "Default")
      (node (ref "LED1") (pin "3") (pinfunction "DO_3") (pintype "output"))
      (node (ref "LED2") (pin "1") (pinfunction "DI_1") (pintype "input"))
    )
    (net (code "38") (name "Net-(LED2-DO)") (class "Default")
      (node (ref "LED2") (pin "3") (pinfunction "DO_3") (pintype "output"))
      (node (ref "LED3") (pin "1") (pinfunction "DI_1") (pintype "input"))
    )
    (net (code "39") (name "Net-(LED3-DO)") (class "Default")
      (node (ref "LED3") (pin "3") (pinfunction "DO_3") (pintype "output"))
      (node (ref "LED4") (pin "1") (pinfunction "DI_1") (pintype "input"))
    )
    (net (code "40") (name "Net-(LED4-DO)") (class "Default")
      (node (ref "LED4") (pin "3") (pinfunction "DO_3") (pintype "output"))
      (node (ref "LED5") (pin "1") (pinfunction "DI_1") (pintype "input"))
    )
    (net (code "41") (name "Net-(LED5-DO)") (class "Default")
      (node (ref "LED5") (pin "3") (pinfunction "DO_3") (pintype "output"))
      (node (ref "LED6") (pin "1") (pinfunction "DI_1") (pintype "input"))
    )
    (net (code "42") (name "Net-(LED6-DO)") (class "Default")
      (node (ref "LED6") (pin "3") (pinfunction "DO_3") (pintype "output"))
      (node (ref "LED7") (pin "1") (pinfunction "DI_1") (pintype "input"))
    )
    (net (code "43") (name "Net-(LED7-DO)") (class "Default")
      (node (ref "LED7") (pin "3") (pinfunction "DO_3") (pintype "output"))
      (node (ref "LED8") (pin "1") (pinfunction "DI_1") (pintype "input"))
    )
    (net (code "44") (name "Net-(LED8-DO)") (class "Default")
      (node (ref "LED8") (pin "3") (pinfunction "DO_3") (pintype "output"))
      (node (ref "LED9") (pin "1") (pinfunction "DI_1") (pintype "input"))
    )
    (net (code "45") (name "Net-(LED10-DI)") (class "Default")
      (node (ref "LED10") (pin "1") (pinfunction "DI_1") (pintype "input"))
      (node (ref "LED9") (pin "3") (pinfunction "DO_3") (pintype "output"))
    )
    (net (code "46") (name "Net-(LED10-DO)") (class "Default")
      (node (ref "LED10") (pin "3") (pinfunction "DO_3") (pintype "output"))
      (node (ref "LED11") (pin "1") (pinfunction "DI_1") (pintype "input"))
    )
    (net (code "47") (name "Net-(LED11-DO)") (class "Default")
      (node (ref "LED11") (pin "3") (pinfunction "DO_3") (pintype "output"))
      (node (ref "LED12") (pin "1") (pinfunction "DI_1") (pintype "input"))
    )
    (net (code "48") (name "Net-(LED12-DO)") (class "Default")
      (node (ref "LED12") (pin "3") (pinfunction "DO_3") (pintype "output"))
      (node (ref "LED14") (pin "1") (pinfunction "DI_1") (pintype "input"))
    )
    (net (code "49") (name "Net-(LED13-DI)") (class "Default")
      (node (ref "LED13") (pin "1") (pinfunction "DI_1") (pintype "input"))
      (node (ref "LED15") (pin "3") (pinfunction "DO_3") (pintype "output"))
    )
    (net (code "50") (name "Net-(LED14-DO)") (class "Default")
      (node (ref "LED14") (pin "3") (pinfunction "DO_3") (pintype "output"))
      (node (ref "LED16") (pin "1") (pinfunction "DI_1") (pintype "input"))
    )
    (net (code "51") (name "Net-(LED15-DI)") (class "Default")
      (node (ref "LED15") (pin "1") (pinfunction "DI_1") (pintype "input"))
      (node (ref "LED17") (pin "3") (pinfunction "DO_3") (pintype "output"))
    )
    (net (code "52") (name "Net-(LED16-DO)") (class "Default")
      (node (ref "LED16") (pin "3") (pinfunction "DO_3") (pintype "output"))
      (node (ref "LED17") (pin "1") (pinfunction "DI_1") (pintype "input"))
    )
    (net (code "53") (name "Net-(R8-11)") (class "Default")
      (node (ref "R8") (pin "1") (pinfunction "11_1") (pintype "passive"))
      (node (ref "U2") (pin "15") (pinfunction "QA_15") (pintype "tri_state"))
    )
    (net (code "54") (name "Net-(R8-23)") (class "Default")
      (node (ref "R8") (pin "2") (pinfunction "23_2") (pintype "passive"))
      (node (ref "U2") (pin "1") (pinfunction "QB_1") (pintype "tri_state"))
    )
    (net (code "55") (name "Net-(R8-35)") (class "Default")
      (node (ref "R8") (pin "3") (pinfunction "35_3") (pintype "passive"))
      (node (ref "U2") (pin "2") (pinfunction "QC_2") (pintype "tri_state"))
    )
    (net (code "56") (name "Net-(R8-47)") (class "Default")
      (node (ref "R8") (pin "4") (pinfunction "47_4") (pintype "passive"))
      (node (ref "U2") (pin "3") (pinfunction "QD_3") (pintype "tri_state"))
    )
    (net (code "57") (name "Net-(R8-516)") (class "Default")
      (node (ref "R8") (pin "5") (pinfunction "516_5") (pintype "passive"))
      (node (ref "U2") (pin "4") (pinfunction "QE_4") (pintype "tri_state"))
    )
    (net (code "58") (name "Net-(R8-615)") (class "Default")
      (node (ref "R8") (pin "6") (pinfunction "615_6") (pintype "passive"))
      (node (ref "U2") (pin "5") (pinfunction "QF_5") (pintype "tri_state"))
    )
    (net (code "59") (name "Net-(R8-714)") (class "Default")
      (node (ref "R8") (pin "7") (pinfunction "714_7") (pintype "passive"))
      (node (ref "U2") (pin "6") (pinfunction "QG_6") (pintype "tri_state"))
    )
    (net (code "60") (name "Net-(R8-813)") (class "Default")
      (node (ref "R8") (pin "8") (pinfunction "813_8") (pintype "passive"))
      (node (ref "U2") (pin "7") (pinfunction "QH_7") (pintype "tri_state"))
    )
    (net (code "61") (name "Net-(SW17-S)") (class "Default")
      (node (ref "R5") (pin "1") (pinfunction "1_1") (pintype "passive"))
      (node (ref "R7") (pin "2") (pinfunction "2_2") (pintype "passive"))
      (node (ref "SW17") (pin "B") (pinfunction "S_B") (pintype "passive"))
      (node (ref "SW17") (pin "B'") (pinfunction "S1_B'") (pintype "passive"))
    )
    (net (code "62") (name "Net-(U$1-IN)") (class "Default")
      (node (ref "R4") (pin "2") (pinfunction "2_2") (pintype "passive"))
      (node (ref "U$1") (pin "1") (pinfunction "IN_1") (pintype "bidirectional"))
      (node (ref "U1") (pin "7") (pinfunction "PB6(XTAL1/TOSC1)_7") (pintype "bidirectional"))
    )
    (net (code "63") (name "Net-(U$1-OUT)") (class "Default")
      (node (ref "R4") (pin "1") (pinfunction "1_1") (pintype "passive"))
      (node (ref "U$1") (pin "3") (pinfunction "OUT_3") (pintype "bidirectional"))
      (node (ref "U1") (pin "8") (pinfunction "PB7(XTAL2/TOSC2)_8") (pintype "bidirectional"))
    )
    (net (code "64") (name "Net-(U$2-A)") (class "Default")
      (node (ref "C21") (pin "2") (pinfunction "2_2") (pintype "passive"))
      (node (ref "R7") (pin "1") (pinfunction "1_1") (pintype "passive"))
      (node (ref "U$2") (pin "2") (pinfunction "A_2") (pintype "input"))
    )
    (net (code "65") (name "Net-(U1-AREF)") (class "Default")
      (node (ref "C24") (pin "2") (pinfunction "2_2") (pintype "passive"))
      (node (ref "U1") (pin "20") (pinfunction "AREF_20") (pintype "bidirectional"))
    )
    (net (code "66") (name "Net-(U4-Y)") (class "Default")
      (node (ref "R12") (pin "2") (pinfunction "2_2") (pintype "passive"))
      (node (ref "U4") (pin "4") (pinfunction "Y_4") (pintype "output"))
    )
    (net (code "67") (name "Net-(U5-Y)") (class "Default")
      (node (ref "R11") (pin "2") (pinfunction "2_2") (pintype "passive"))
      (node (ref "U5") (pin "4") (pinfunction "Y_4") (pintype "output"))
    )
    (net (code "68") (name "Net-(U6-A)") (class "Default")
      (node (ref "J4") (pin "1") (pinfunction "1_1") (pintype "passive"))
      (node (ref "U6") (pin "2") (pinfunction "A_2") (pintype "bidirectional"))
    )
    (net (code "69") (name "RESET") (class "Default")
      (node (ref "C23") (pin "2") (pinfunction "2_2") (pintype "passive"))
      (node (ref "R1") (pin "2") (pinfunction "2_2") (pintype "passive"))
      (node (ref "U1") (pin "29") (pinfunction "PC6(/RESET)_29") (pintype "bidirectional"))
    )
    (net (code "70") (name "SCK") (class "Default")
      (node (ref "J3") (pin "3") (pinfunction "3_3") (pintype "bidirectional"))
      (node (ref "U1") (pin "17") (pinfunction "PB5(SCK)_17") (pintype "bidirectional"))
    )
    (net (code "71") (name "VCC") (class "Default")
      (node (ref "C1") (pin "1") (pinfunction "1_1") (pintype "passive"))
      (node (ref "C10") (pin "1") (pinfunction "1_1") (pintype "passive"))
      (node (ref "C11") (pin "1") (pinfunction "1_1") (pintype "passive"))
      (node (ref "C12") (pin "1") (pinfunction "1_1") (pintype "passive"))
      (node (ref "C13") (pin "1") (pinfunction "1_1") (pintype "passive"))
      (node (ref "C14") (pin "1") (pinfunction "1_1") (pintype "passive"))
      (node (ref "C15") (pin "1") (pinfunction "1_1") (pintype "passive"))
      (node (ref "C16") (pin "1") (pinfunction "1_1") (pintype "passive"))
      (node (ref "C17") (pin "1") (pinfunction "1_1") (pintype "passive"))
      (node (ref "C18") (pin "1") (pinfunction "1_1") (pintype "passive"))
      (node (ref "C19") (pin "1") (pinfunction "1_1") (pintype "passive"))
      (node (ref "C2") (pin "1") (pinfunction "1_1") (pintype "passive"))
      (node (ref "C20") (pin "1") (pinfunction "1_1") (pintype "passive"))
      (node (ref "C22") (pin "+") (pinfunction "+_+") (pintype "passive"))
      (node (ref "C3") (pin "1") (pinfunction "1_1") (pintype "passive"))
      (node (ref "C4") (pin "1") (pinfunction "1_1") (pintype "passive"))
      (node (ref "C5") (pin "1") (pinfunction "1_1") (pintype "passive"))
      (node (ref "C6") (pin "1") (pinfunction "1_1") (pintype "passive"))
      (node (ref "C7") (pin "1") (pinfunction "1_1") (pintype "passive"))
      (node (ref "C8") (pin "1") (pinfunction "1_1") (pintype "passive"))
      (node (ref "C9") (pin "1") (pinfunction "1_1") (pintype "passive"))
      (node (ref "D1") (pin "7SEG3") (pinfunction "CA1_7SEG3") (pintype "passive"))
      (node (ref "D1") (pin "7SEG8") (pinfunction "CA2_7SEG8") (pintype "passive"))
      (node (ref "F1") (pin "2") (pinfunction "2_2") (pintype "bidirectional"))
      (node (ref "J3") (pin "1") (pinfunction "1_1") (pintype "bidirectional"))
      (node (ref "LED1") (pin "2") (pinfunction "VDD_2") (pintype "power_in"))
      (node (ref "LED10") (pin "2") (pinfunction "VDD_2") (pintype "power_in"))
      (node (ref "LED11") (pin "2") (pinfunction "VDD_2") (pintype "power_in"))
      (node (ref "LED12") (pin "2") (pinfunction "VDD_2") (pintype "power_in"))
      (node (ref "LED13") (pin "2") (pinfunction "VDD_2") (pintype "power_in"))
      (node (ref "LED14") (pin "2") (pinfunction "VDD_2") (pintype "power_in"))
      (node (ref "LED15") (pin "2") (pinfunction "VDD_2") (pintype "power_in"))
      (node (ref "LED16") (pin "2") (pinfunction "VDD_2") (pintype "power_in"))
      (node (ref "LED17") (pin "2") (pinfunction "VDD_2") (pintype "power_in"))
      (node (ref "LED2") (pin "2") (pinfunction "VDD_2") (pintype "power_in"))
      (node (ref "LED3") (pin "2") (pinfunction "VDD_2") (pintype "power_in"))
      (node (ref "LED4") (pin "2") (pinfunction "VDD_2") (pintype "power_in"))
      (node (ref "LED5") (pin "2") (pinfunction "VDD_2") (pintype "power_in"))
      (node (ref "LED6") (pin "2") (pinfunction "VDD_2") (pintype "power_in"))
      (node (ref "LED7") (pin "2") (pinfunction "VDD_2") (pintype "power_in"))
      (node (ref "LED8") (pin "2") (pinfunction "VDD_2") (pintype "power_in"))
      (node (ref "LED9") (pin "2") (pinfunction "VDD_2") (pintype "power_in"))
      (node (ref "R1") (pin "1") (pinfunction "1_1") (pintype "passive"))
      (node (ref "R10") (pin "2") (pinfunction "2_2") (pintype "passive"))
      (node (ref "R5") (pin "2") (pinfunction "2_2") (pintype "passive"))
      (node (ref "R6") (pin "2") (pinfunction "2_2") (pintype "passive"))
      (node (ref "R9") (pin "2") (pinfunction "2_2") (pintype "passive"))
      (node (ref "U$2") (pin "5") (pinfunction "VCC_5") (pintype "power_in"))
      (node (ref "U1") (pin "18") (pinfunction "AVCC_18") (pintype "bidirectional"))
      (node (ref "U1") (pin "4") (pinfunction "VCC_4") (pintype "bidirectional"))
      (node (ref "U1") (pin "6") (pinfunction "VCC_6") (pintype "bidirectional"))
      (node (ref "U2") (pin "10") (pinfunction "SCL_10") (pintype "input"))
      (node (ref "U2") (pin "16") (pinfunction "VCC_16") (pintype "power_in"))
      (node (ref "U4") (pin "5") (pinfunction "VCC_5") (pintype "power_in"))
      (node (ref "U5") (pin "5") (pinfunction "VCC_5") (pintype "power_in"))
      (node (ref "U6") (pin "7") (pinfunction "EN_7") (pintype "bidirectional"))
      (node (ref "U6") (pin "8") (pinfunction "VCC_8") (pintype "bidirectional"))
      (node (ref "V1") (pin "2") (pinfunction "2_2") (pintype "passive"))
    )
    (net (code "72") (name "unconnected-(CN1-PadD+)") (class "Default")
      (node (ref "CN1") (pin "D+") (pinfunction "D+_D+") (pintype "bidirectional"))
    )
    (net (code "73") (name "unconnected-(CN1-PadD-)") (class "Default")
      (node (ref "CN1") (pin "D-") (pinfunction "D-_D-") (pintype "bidirectional"))
    )
    (net (code "74") (name "unconnected-(CN1-PadID)") (class "Default")
      (node (ref "CN1") (pin "ID") (pinfunction "ID_ID") (pintype "bidirectional"))
    )
    (net (code "75") (name "unconnected-(U$2-NC-Pad1)") (class "Default")
      (node (ref "U$2") (pin "1") (pinfunction "NC_1") (pintype "no_connect"))
    )
    (net (code "76") (name "unconnected-(U1-ADC6-Pad19)") (class "Default")
      (node (ref "U1") (pin "19") (pinfunction "ADC6_19") (pintype "bidirectional"))
    )
    (net (code "77") (name "unconnected-(U1-ADC7-Pad22)") (class "Default")
      (node (ref "U1") (pin "22") (pinfunction "ADC7_22") (pintype "bidirectional"))
    )
    (net (code "78") (name "unconnected-(U2-QH*-Pad9)") (class "Default")
      (node (ref "U2") (pin "9") (pinfunction "QH*_9") (pintype "tri_state"))
    )
  )
)
